# POWER.net
KiCad netlist of a schematic drawn in Altium Designer
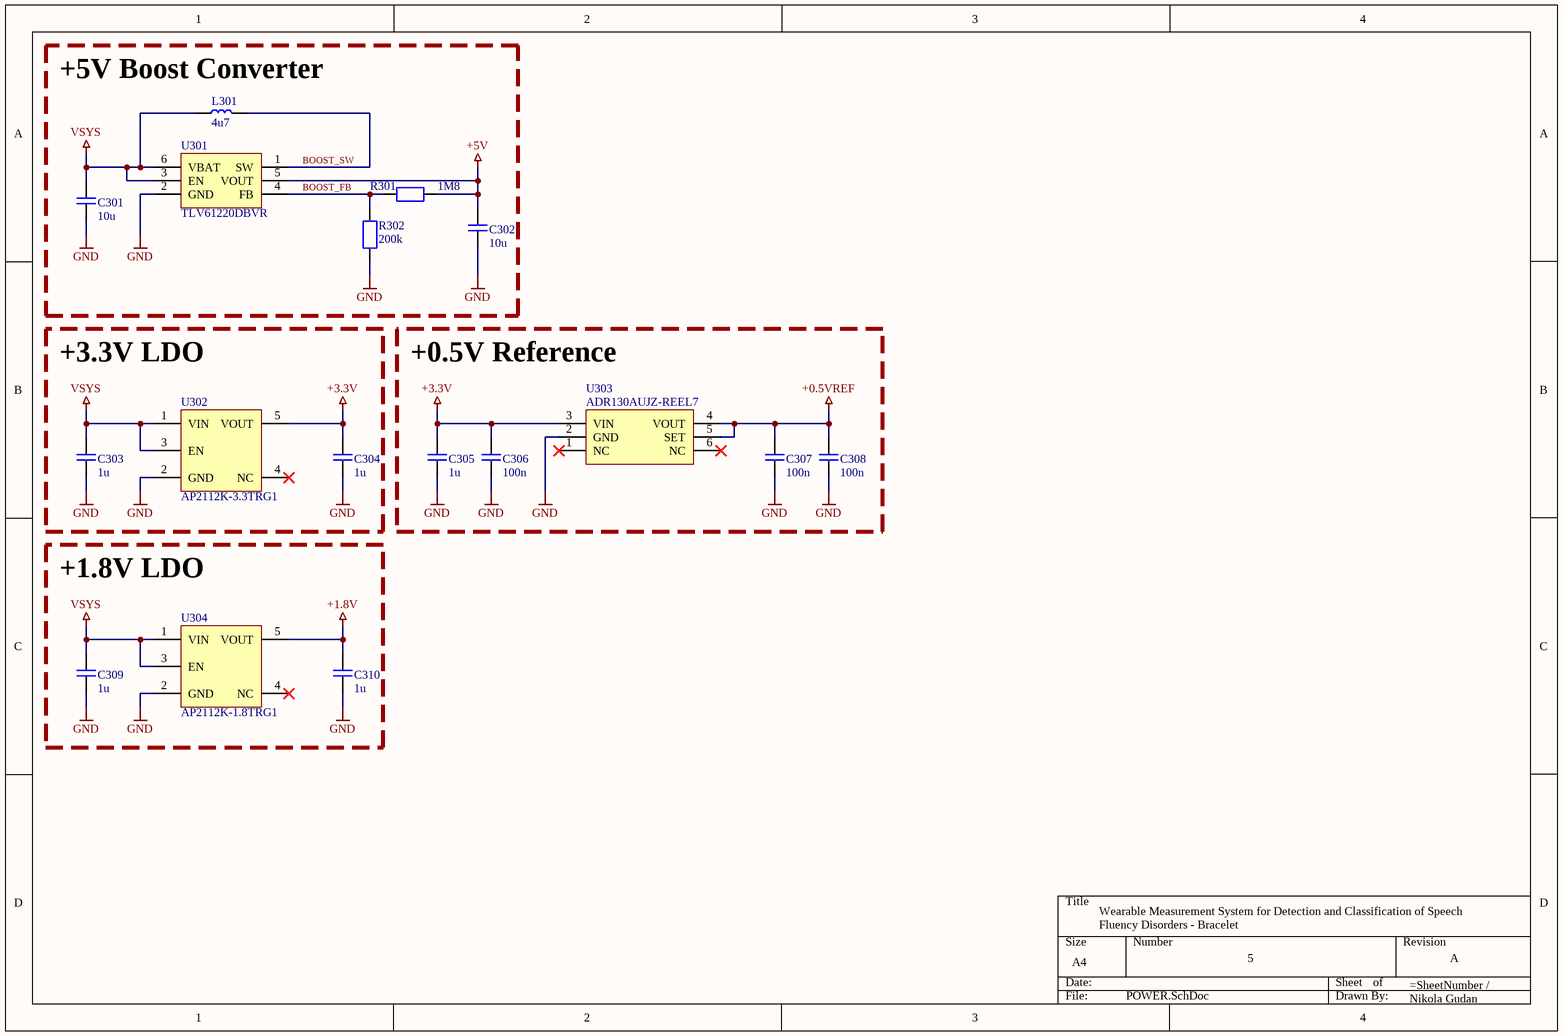
[diagram p0: POWER.SchDoc]

(export (version "E")
  (design (tool "Eeschema 10.0.6"))
  (components
    (comp (ref "C301")
      (value "10u")
      (footprint "CAPC0603")
      (description "Ceramic capacitor, 10uF,  25V, X5R")
      (fields (field (name "MFR") "TAIYO YUDEN") (field (name "CHECKED") "Yes"))
      (libsource (lib "NG_Passive") (part "CAPC0603-10u-20"))
    )
    (comp (ref "C302")
      (value "10u")
      (footprint "CAPC0603")
      (description "Ceramic capacitor, 10uF,  25V, X5R")
      (fields (field (name "MFR") "TAIYO YUDEN") (field (name "CHECKED") "Yes"))
      (libsource (lib "NG_Passive") (part "CAPC0603-10u-20"))
    )
    (comp (ref "C303")
      (value "1u")
      (footprint "CAPC0603")
      (description "Ceramic capacitor, 1uF,  50V, X5R")
      (fields (field (name "MFR") "Murata Electronics") (field (name "CHECKED") "Yes"))
      (libsource (lib "NG_Passive") (part "CAPC0603-1u-10"))
    )
    (comp (ref "C304")
      (value "1u")
      (footprint "CAPC0603")
      (description "Ceramic capacitor, 1uF,  50V, X5R")
      (fields (field (name "MFR") "Murata Electronics") (field (name "CHECKED") "Yes"))
      (libsource (lib "NG_Passive") (part "CAPC0603-1u-10"))
    )
    (comp (ref "C305")
      (value "1u")
      (footprint "CAPC0603")
      (description "Ceramic capacitor, 1uF,  50V, X5R")
      (fields (field (name "MFR") "Murata Electronics") (field (name "CHECKED") "Yes"))
      (libsource (lib "NG_Passive") (part "CAPC0603-1u-10"))
    )
    (comp (ref "C306")
      (value "100n")
      (footprint "CAPC0603")
      (description "Ceramic capacitor, 100nF,  50V, X7R")
      (fields (field (name "MFR") "KEMET") (field (name "CHECKED") "Yes"))
      (libsource (lib "NG_Passive") (part "CAPC0603-100n-10"))
    )
    (comp (ref "C307")
      (value "100n")
      (footprint "CAPC0603")
      (description "Ceramic capacitor, 100nF,  50V, X7R")
      (fields (field (name "MFR") "KEMET") (field (name "CHECKED") "Yes"))
      (libsource (lib "NG_Passive") (part "CAPC0603-100n-10"))
    )
    (comp (ref "C308")
      (value "100n")
      (footprint "CAPC0603")
      (description "Ceramic capacitor, 100nF,  50V, X7R")
      (fields (field (name "MFR") "KEMET") (field (name "CHECKED") "Yes"))
      (libsource (lib "NG_Passive") (part "CAPC0603-100n-10"))
    )
    (comp (ref "C309")
      (value "1u")
      (footprint "CAPC0603")
      (description "Ceramic capacitor, 1uF,  50V, X5R")
      (fields (field (name "MFR") "Murata Electronics") (field (name "CHECKED") "Yes"))
      (libsource (lib "NG_Passive") (part "CAPC0603-1u-10"))
    )
    (comp (ref "C310")
      (value "1u")
      (footprint "CAPC0603")
      (description "Ceramic capacitor, 1uF,  50V, X5R")
      (fields (field (name "MFR") "Murata Electronics") (field (name "CHECKED") "Yes"))
      (libsource (lib "NG_Passive") (part "CAPC0603-1u-10"))
    )
    (comp (ref "L301")
      (value "4u7")
      (footprint "INDC1007")
      (description "Inductor 4.7uH, 680mA, ±20%, 260mOhm")
      (fields (field (name "MFR") "TAIYO YUDEN") (field (name "CHECKED") "Yes"))
      (libsource (lib "NG_Passive") (part "INDC1007-4u7-20"))
    )
    (comp (ref "R301")
      (value "1M8")
      (footprint "RESC0603")
      (description "Thick film resistor, 1.8MOhms, 100mW")
      (fields (field (name "MFR") "Vishay / Dale") (field (name "CHECKED") "Yes"))
      (libsource (lib "NG_Passive") (part "RES0603-1M8-1"))
    )
    (comp (ref "R302")
      (value "200k")
      (footprint "RESC0603")
      (description "Thick film resistor, 200kOhms, 100mW")
      (fields (field (name "MFR") "YAGEO") (field (name "CHECKED") "Yes"))
      (libsource (lib "NG_Passive") (part "RES0603-200k-1"))
    )
    (comp (ref "U301")
      (value "TLV61220DBVR")
      (footprint "SOT95P280X115-6")
      (description "Boost converter, 0.7V to 5.5V Input")
      (fields (field (name "MFR") "Texas Instruments") (field (name "CHECKED") "No"))
      (libsource (lib "NG_Analog") (part "BOOST TLV61220DBVR"))
    )
    (comp (ref "U302")
      (value "AP2112K-3.3TRG1")
      (footprint "SOT95P280X115-5")
      (description "Linear LDO Voltage Regulator, 3.3V, 600mA")
      (fields (field (name "MFR") "Diodes Incorporated") (field (name "CHECKED") "Yes"))
      (libsource (lib "NG_Analog") (part "IC REG LINEAR AP2112K-3.3TRG1"))
    )
    (comp (ref "U303")
      (value "ADR130AUJZ-REEL7")
      (footprint "SOT95P280X115-6")
      (description "Voltage reference, 0.5V or 1V")
      (fields (field (name "MFR") "Analog Devices") (field (name "CHECKED") "No"))
      (libsource (lib "NG_Analog") (part "IC VREF ADR130AUJZ-REEL7"))
    )
    (comp (ref "U304")
      (value "AP2112K-1.8TRG1")
      (footprint "SOT95P280X115-5")
      (description "Linear LDO Voltage Regulator, 1.8V, 600mA")
      (fields (field (name "MFR") "Diodes Incorporated") (field (name "CHECKED") "Yes"))
      (libsource (lib "NG_Analog") (part "IC REG LINEAR AP2112K-1.8TRG1"))
    )
  )
  (nets
    (net (code "1") (name "+0.5VREF") (class "Default")
      (node (ref "C307") (pin "2") (pinfunction "2_2") (pintype "passive"))
      (node (ref "C308") (pin "2") (pinfunction "2_2") (pintype "passive"))
      (node (ref "U303") (pin "4") (pinfunction "VOUT_4") (pintype "power_in"))
      (node (ref "U303") (pin "5") (pinfunction "SET_5") (pintype "passive"))
    )
    (net (code "2") (name "+1.8V") (class "Default")
      (node (ref "C310") (pin "2") (pinfunction "2_2") (pintype "passive"))
      (node (ref "U304") (pin "5") (pinfunction "VOUT_5") (pintype "passive"))
    )
    (net (code "3") (name "+3.3V") (class "Default")
      (node (ref "C304") (pin "2") (pinfunction "2_2") (pintype "passive"))
      (node (ref "C305") (pin "2") (pinfunction "2_2") (pintype "passive"))
      (node (ref "C306") (pin "2") (pinfunction "2_2") (pintype "passive"))
      (node (ref "U302") (pin "5") (pinfunction "VOUT_5") (pintype "passive"))
      (node (ref "U303") (pin "3") (pinfunction "VIN_3") (pintype "power_in"))
    )
    (net (code "4") (name "+5V") (class "Default")
      (node (ref "C302") (pin "2") (pinfunction "2_2") (pintype "passive"))
      (node (ref "R301") (pin "2") (pinfunction "2_2") (pintype "passive"))
      (node (ref "U301") (pin "5") (pinfunction "VOUT_5") (pintype "power_in"))
    )
    (net (code "5") (name "/BOOST_FB") (class "Default")
      (node (ref "R301") (pin "1") (pinfunction "1_1") (pintype "passive"))
      (node (ref "R302") (pin "2") (pinfunction "2_2") (pintype "passive"))
      (node (ref "U301") (pin "4") (pinfunction "FB_4") (pintype "passive"))
    )
    (net (code "6") (name "/BOOST_SW") (class "Default")
      (node (ref "L301") (pin "2") (pinfunction "2_2") (pintype "passive"))
      (node (ref "U301") (pin "1") (pinfunction "SW_1") (pintype "power_in"))
    )
    (net (code "7") (name "GND") (class "Default")
      (node (ref "C301") (pin "1") (pinfunction "1_1") (pintype "passive"))
      (node (ref "C302") (pin "1") (pinfunction "1_1") (pintype "passive"))
      (node (ref "C303") (pin "1") (pinfunction "1_1") (pintype "passive"))
      (node (ref "C304") (pin "1") (pinfunction "1_1") (pintype "passive"))
      (node (ref "C305") (pin "1") (pinfunction "1_1") (pintype "passive"))
      (node (ref "C306") (pin "1") (pinfunction "1_1") (pintype "passive"))
      (node (ref "C307") (pin "1") (pinfunction "1_1") (pintype "passive"))
      (node (ref "C308") (pin "1") (pinfunction "1_1") (pintype "passive"))
      (node (ref "C309") (pin "1") (pinfunction "1_1") (pintype "passive"))
      (node (ref "C310") (pin "1") (pinfunction "1_1") (pintype "passive"))
      (node (ref "R302") (pin "1") (pinfunction "1_1") (pintype "passive"))
      (node (ref "U301") (pin "2") (pinfunction "GND_2") (pintype "power_in"))
      (node (ref "U302") (pin "2") (pinfunction "GND_2") (pintype "power_in"))
      (node (ref "U303") (pin "2") (pinfunction "GND_2") (pintype "power_in"))
      (node (ref "U304") (pin "2") (pinfunction "GND_2") (pintype "power_in"))
    )
    (net (code "8") (name "VSYS") (class "Default")
      (node (ref "C301") (pin "2") (pinfunction "2_2") (pintype "passive"))
      (node (ref "C303") (pin "2") (pinfunction "2_2") (pintype "passive"))
      (node (ref "C309") (pin "2") (pinfunction "2_2") (pintype "passive"))
      (node (ref "L301") (pin "1") (pinfunction "1_1") (pintype "passive"))
      (node (ref "U301") (pin "3") (pinfunction "EN_3") (pintype "passive"))
      (node (ref "U301") (pin "6") (pinfunction "VBAT_6") (pintype "power_in"))
      (node (ref "U302") (pin "1") (pinfunction "VIN_1") (pintype "power_in"))
      (node (ref "U302") (pin "3") (pinfunction "EN_3") (pintype "power_in"))
      (node (ref "U304") (pin "1") (pinfunction "VIN_1") (pintype "power_in"))
      (node (ref "U304") (pin "3") (pinfunction "EN_3") (pintype "power_in"))
    )
    (net (code "9") (name "unconnected-(U302-NC-Pad4)") (class "Default")
      (node (ref "U302") (pin "4") (pinfunction "NC_4") (pintype "passive+no_connect"))
    )
    (net (code "10") (name "unconnected-(U303-NC-Pad1)") (class "Default")
      (node (ref "U303") (pin "1") (pinfunction "NC_1") (pintype "passive+no_connect"))
    )
    (net (code "11") (name "unconnected-(U303-NC-Pad6)") (class "Default")
      (node (ref "U303") (pin "6") (pinfunction "NC_6") (pintype "passive+no_connect"))
    )
    (net (code "12") (name "unconnected-(U304-NC-Pad4)") (class "Default")
      (node (ref "U304") (pin "4") (pinfunction "NC_4") (pintype "passive+no_connect"))
    )
  )
)
